# Rbot-sensor-driver.net
KiCad netlist of a schematic drawn in Altium Designer
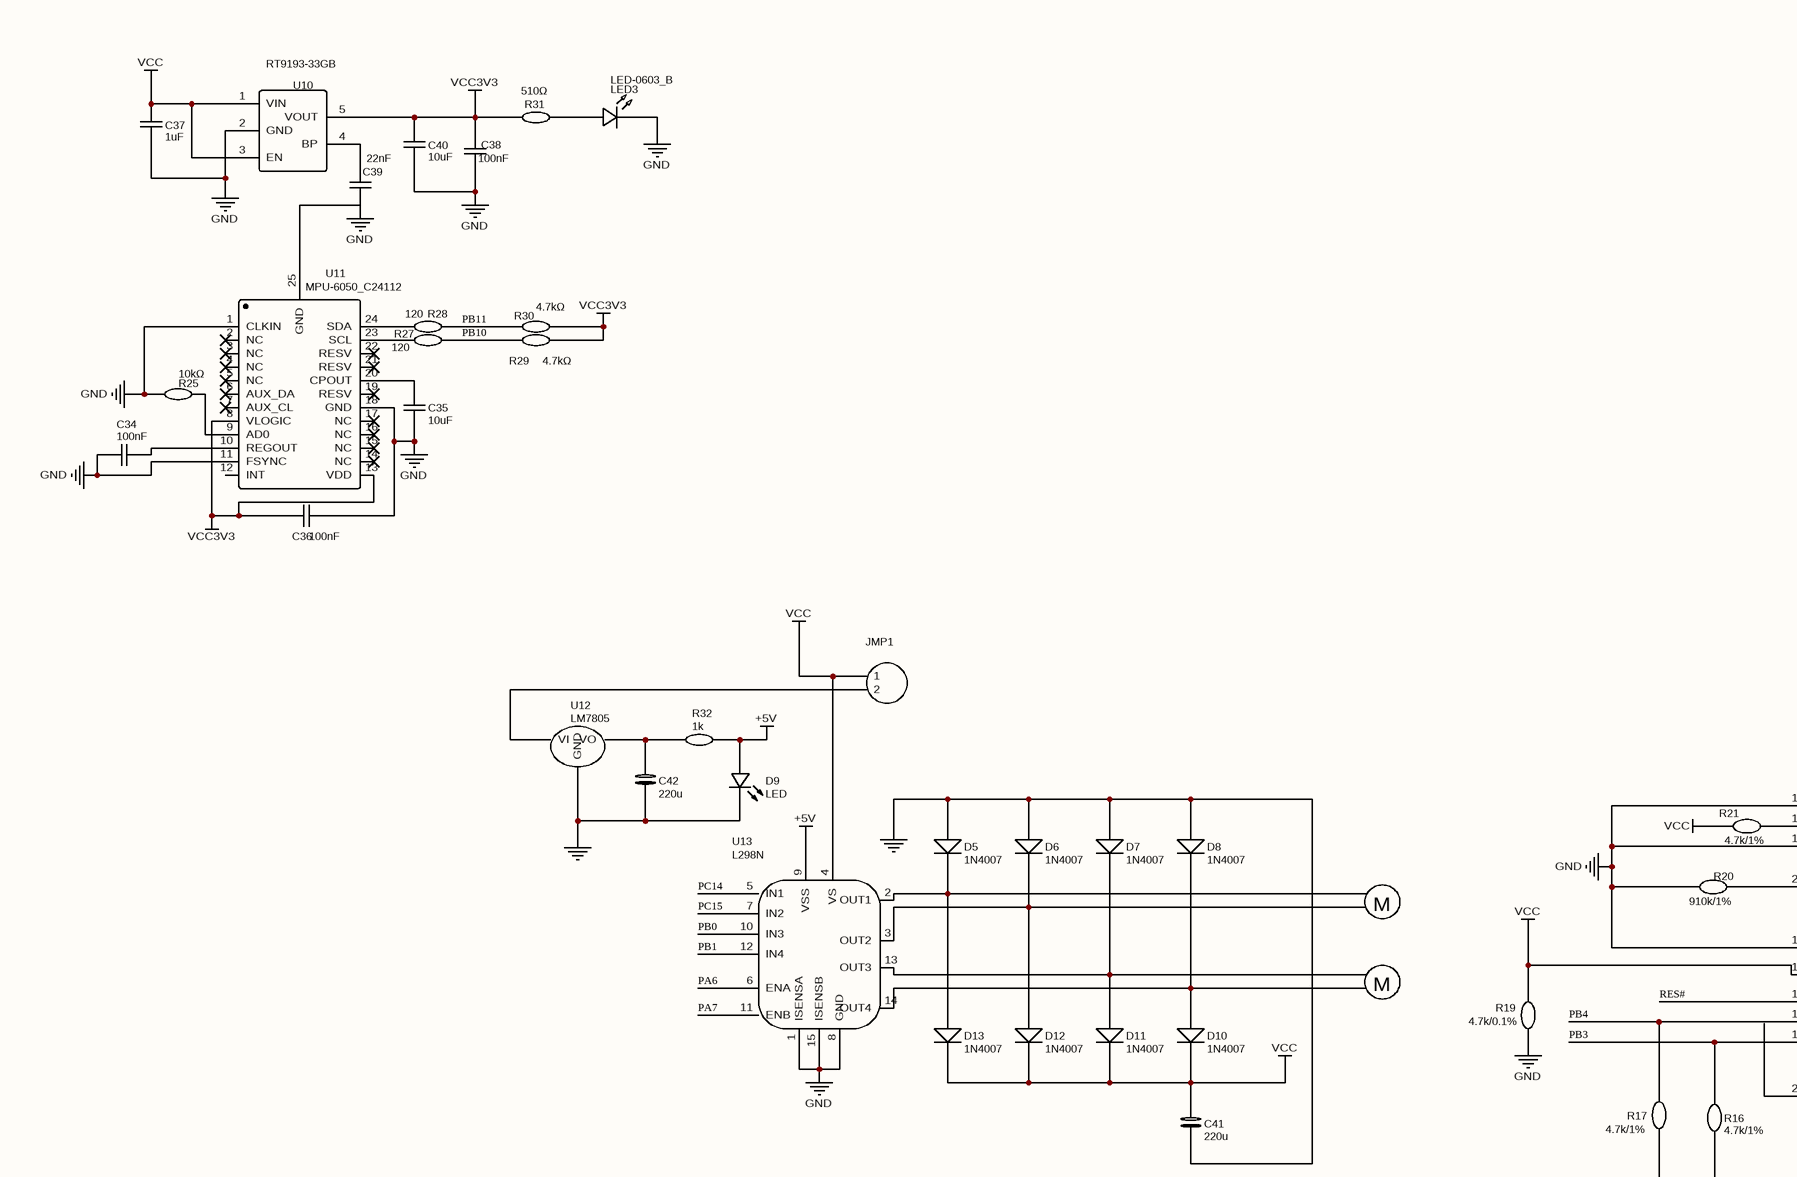
[diagram p0: Rbot-sensor-driver.schdoc, top left]
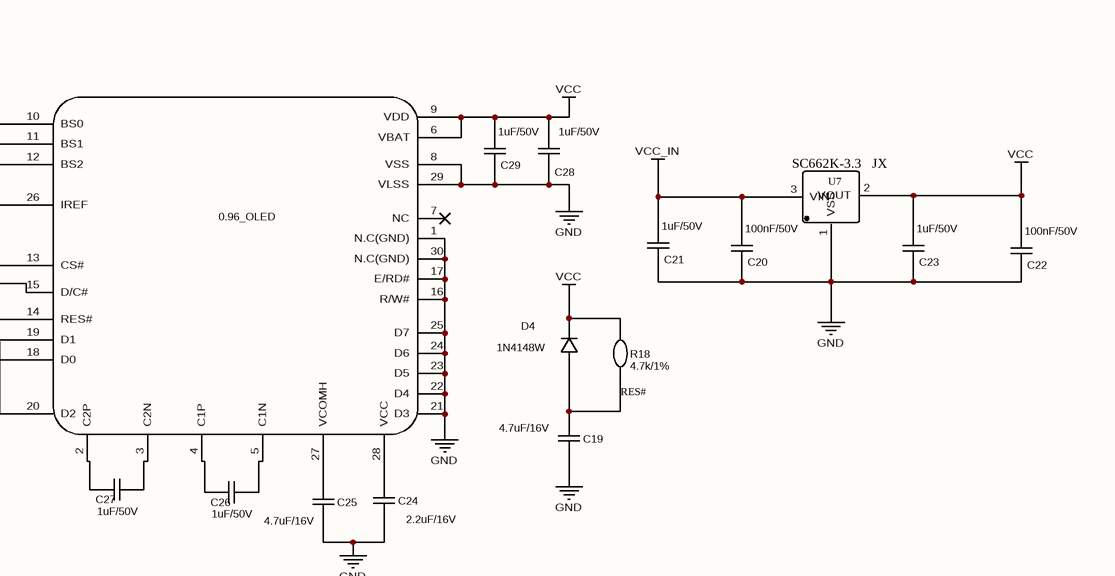
[diagram p1: Rbot-sensor-driver.schdoc, top right]
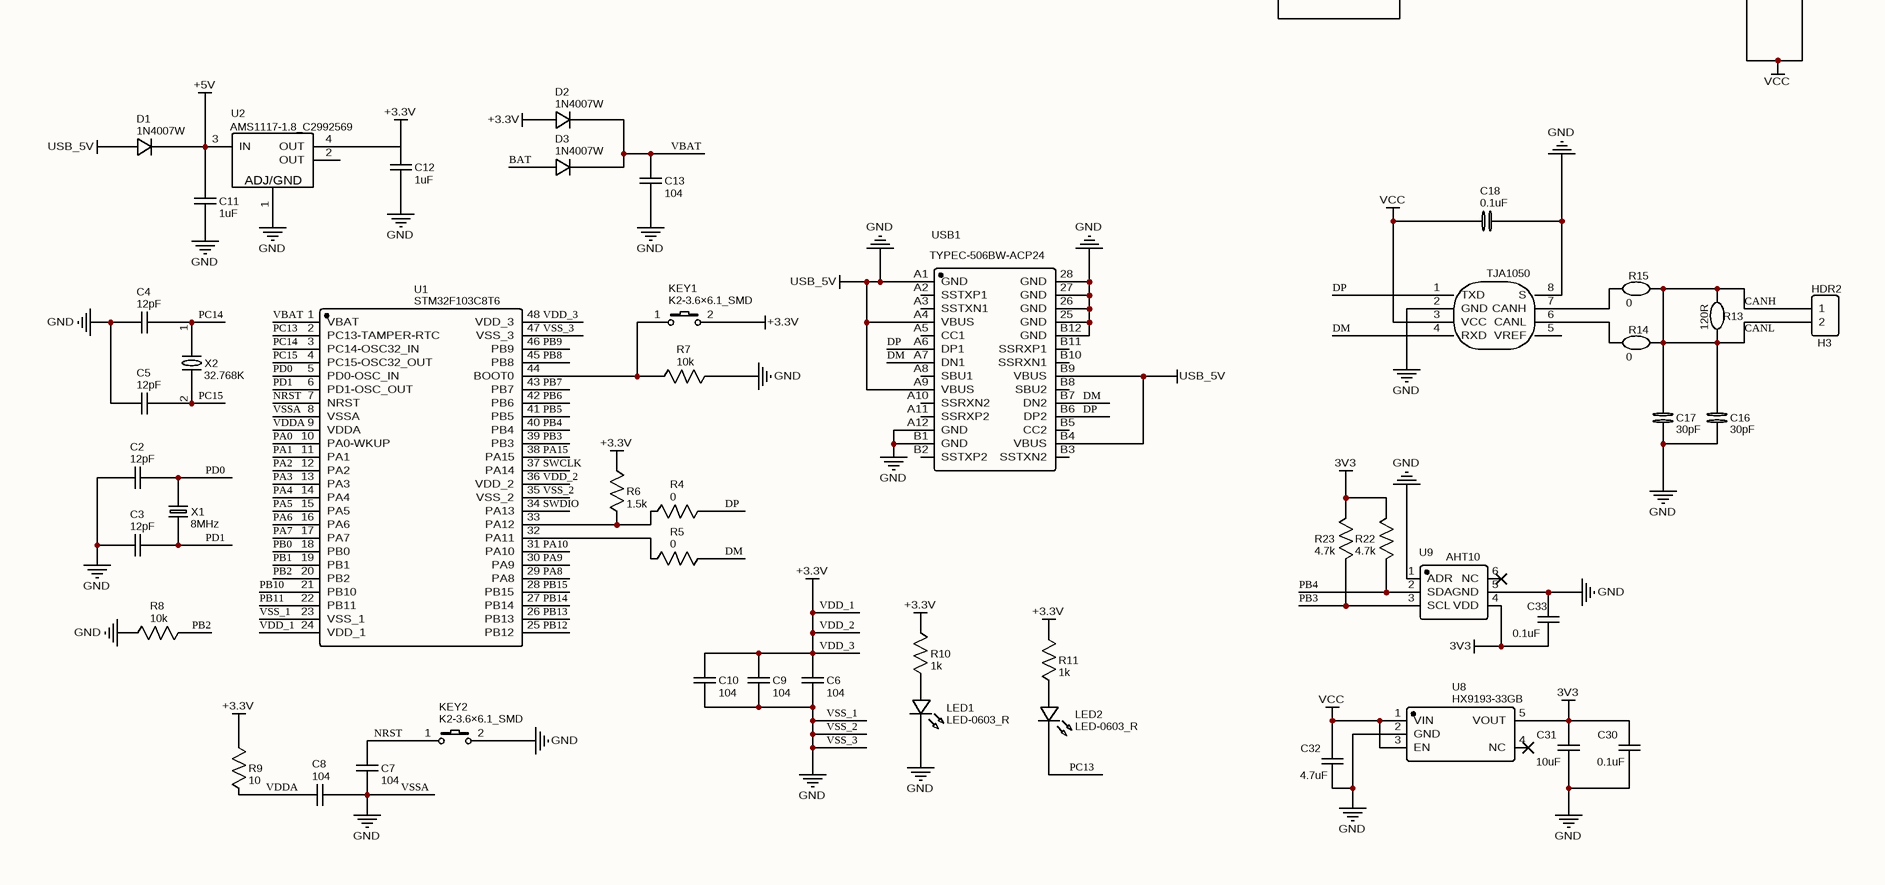
[diagram p2: Rbot-sensor-driver.schdoc, bottom left]

(export (version "E")
  (design (tool "Eeschema 10.0.6"))
  (components
    (comp (ref "0.96_OLED")
      (value "0.96-OLED")
      (footprint "SSD1306-30PIN-JX")
      (libsource (lib "altium-import") (part "root_0_0.96-OLED_"))
    )
    (comp (ref "C2")
      (value "12pF")
      (footprint "C0603")
      (libsource (lib "altium-import") (part "root_0_12pF_"))
    )
    (comp (ref "C3")
      (value "12pF")
      (footprint "C0603")
      (libsource (lib "altium-import") (part "root_0_12pF_"))
    )
    (comp (ref "C4")
      (value "12pF")
      (footprint "C0603")
      (libsource (lib "altium-import") (part "root_0_12pF_"))
    )
    (comp (ref "C5")
      (value "12pF")
      (footprint "C0603")
      (libsource (lib "altium-import") (part "root_0_12pF_"))
    )
    (comp (ref "C6") (value "104") (footprint "C0603") (libsource (lib "altium-import") (part "root_1_104_")))
    (comp (ref "C7") (value "104") (footprint "C0603") (libsource (lib "altium-import") (part "root_1_104_")))
    (comp (ref "C8") (value "104") (footprint "C0603") (libsource (lib "altium-import") (part "root_2_104_")))
    (comp (ref "C9") (value "104") (footprint "C0603") (libsource (lib "altium-import") (part "root_1_104_")))
    (comp (ref "C10")
      (value "104")
      (footprint "C0603")
      (libsource (lib "altium-import") (part "root_1_104_"))
    )
    (comp (ref "C11")
      (value "1uF")
      (footprint "C0603")
      (libsource (lib "altium-import") (part "root_3_1uF_"))
    )
    (comp (ref "C12")
      (value "1uF")
      (footprint "C0603")
      (libsource (lib "altium-import") (part "root_3_1uF_"))
    )
    (comp (ref "C13")
      (value "104")
      (footprint "C0603")
      (libsource (lib "altium-import") (part "root_3_104_"))
    )
    (comp (ref "C16")
      (value "30pF")
      (footprint "C0603")
      (libsource (lib "altium-import") (part "root_1_30pF_"))
    )
    (comp (ref "C17")
      (value "30pF")
      (footprint "C0603")
      (libsource (lib "altium-import") (part "root_1_30pF_"))
    )
    (comp (ref "C18")
      (value "0.1uF")
      (footprint "C0603")
      (libsource (lib "altium-import") (part "root_0_0.1uF_"))
    )
    (comp (ref "C19")
      (value "4.7uF/16V")
      (footprint "0603_C_JX")
      (libsource (lib "altium-import") (part "root_2_4.7uF/16V_"))
    )
    (comp (ref "C20")
      (value "100nF/50V")
      (footprint "0603_C_JX")
      (libsource (lib "altium-import") (part "root_0_100nF/50V_"))
    )
    (comp (ref "C21")
      (value "1uF/50V")
      (footprint "0603_C_JX")
      (libsource (lib "altium-import") (part "root_0_1uF/50V_"))
    )
    (comp (ref "C22")
      (value "100nF/50V")
      (footprint "0603_C_JX")
      (libsource (lib "altium-import") (part "root_0_100nF/50V_"))
    )
    (comp (ref "C23")
      (value "1uF/50V")
      (footprint "0603_C_JX")
      (libsource (lib "altium-import") (part "root_0_1uF/50V_"))
    )
    (comp (ref "C24")
      (value "2.2uF/16V")
      (footprint "0603_C_JX")
      (libsource (lib "altium-import") (part "root_2_2.2uF/16V_"))
    )
    (comp (ref "C25")
      (value "4.7uF/16V")
      (footprint "0603_C_JX")
      (libsource (lib "altium-import") (part "root_2_4.7uF/16V_"))
    )
    (comp (ref "C26")
      (value "1uF/50V")
      (footprint "0603_C_JX")
      (libsource (lib "altium-import") (part "root_1_1uF/50V_"))
    )
    (comp (ref "C27")
      (value "1uF/50V")
      (footprint "0603_C_JX")
      (libsource (lib "altium-import") (part "root_1_1uF/50V_"))
    )
    (comp (ref "C28")
      (value "1uF/50V")
      (footprint "0603_C_JX")
      (libsource (lib "altium-import") (part "root_0_1uF/50V_"))
    )
    (comp (ref "C29")
      (value "1uF/50V")
      (footprint "0603_C_JX")
      (libsource (lib "altium-import") (part "root_0_1uF/50V_"))
    )
    (comp (ref "C30")
      (value "0.1uF")
      (footprint "C0402")
      (libsource (lib "altium-import") (part "root_1_0.1uF_"))
    )
    (comp (ref "C31")
      (value "10uF")
      (footprint "C0402")
      (libsource (lib "altium-import") (part "root_1_10uF_"))
    )
    (comp (ref "C32")
      (value "4.7uF")
      (footprint "C0402")
      (libsource (lib "altium-import") (part "root_1_4.7uF_"))
    )
    (comp (ref "C33")
      (value "0.1uF")
      (footprint "C0402")
      (libsource (lib "altium-import") (part "root_1_0.1uF_"))
    )
    (comp (ref "C34")
      (value "100nF")
      (footprint "C0805")
      (fields
        (field (name "MANUFACTURER") "HEC(Holy Stone Enterprise)")
        (field (name "MANUFACTURER PART") "C0805X104K101T")
      )
      (libsource (lib "altium-import") (part "root_1_100nF_"))
    )
    (comp (ref "C35")
      (value "10uF")
      (footprint "C0805")
      (fields
        (field (name "MANUFACTURER") "muRata(村田)")
        (field (name "MANUFACTURER PART") "GRT21BC71E106KE13L")
      )
      (libsource (lib "altium-import") (part "root_1_10uF_"))
    )
    (comp (ref "C36")
      (value "100nF")
      (footprint "C0805")
      (fields
        (field (name "MANUFACTURER") "HEC(Holy Stone Enterprise)")
        (field (name "MANUFACTURER PART") "C0805X104K101T")
      )
      (libsource (lib "altium-import") (part "root_1_100nF_"))
    )
    (comp (ref "C37")
      (value "1uF")
      (footprint "C0805")
      (fields (field (name "MANUFACTURER PART") "CL21F105ZBFNNNE") (field (name "MANUFACTURER") "SAMSUNG"))
      (libsource (lib "altium-import") (part "root_1_1uF_"))
    )
    (comp (ref "C38")
      (value "100nF")
      (footprint "C0805")
      (fields
        (field (name "MANUFACTURER") "HEC(Holy Stone Enterprise)")
        (field (name "MANUFACTURER PART") "C0805X104K101T")
      )
      (libsource (lib "altium-import") (part "root_0_100nF_"))
    )
    (comp (ref "C39")
      (value "22nF")
      (footprint "C0805")
      (fields (field (name "MANUFACTURER") "Huaxin S&T") (field (name "MANUFACTURER PART") "0805B223K251CT"))
      (libsource (lib "altium-import") (part "root_0_22nF_"))
    )
    (comp (ref "C40")
      (value "10uF")
      (footprint "C0805")
      (fields
        (field (name "MANUFACTURER") "muRata(村田)")
        (field (name "MANUFACTURER PART") "GRT21BC71E106KE13L")
      )
      (libsource (lib "altium-import") (part "root_1_10uF_"))
    )
    (comp (ref "C41")
      (value "220u")
      (footprint "CP_8X13MM")
      (fields (field (name "MANUFACTURER PART") "?"))
      (libsource (lib "altium-import") (part "root_0_220u_"))
    )
    (comp (ref "C42")
      (value "220u")
      (footprint "CP_8X13MM")
      (fields (field (name "MANUFACTURER PART") "?"))
      (libsource (lib "altium-import") (part "root_0_220u_"))
    )
    (comp (ref "D1")
      (value "1N4007W")
      (footprint "SOD-123_L2.8-W1.8-LS3.7-RD")
      (fields (field (name "MANUFACTURER") "BLUE ROCKET"))
      (libsource (lib "altium-import") (part "root_0_1N4007W_"))
    )
    (comp (ref "D2")
      (value "1N4007W")
      (footprint "SOD-123_L2.8-W1.8-LS3.7-RD")
      (fields (field (name "MANUFACTURER") "BLUE ROCKET"))
      (libsource (lib "altium-import") (part "root_0_1N4007W_"))
    )
    (comp (ref "D3")
      (value "1N4007W")
      (footprint "SOD-123_L2.8-W1.8-LS3.7-RD")
      (fields (field (name "MANUFACTURER") "BLUE ROCKET"))
      (libsource (lib "altium-import") (part "root_0_1N4007W_"))
    )
    (comp (ref "D4")
      (value "1N4148W")
      (footprint "SOD-523_JX")
      (fields (field (name "MANUFACTURER") "SEMTECH"))
      (libsource (lib "altium-import") (part "root_3_1N4148W_"))
    )
    (comp (ref "D5")
      (value "1N4007")
      (footprint "DO-41")
      (fields (field (name "MANUFACTURER PART") "?"))
      (libsource (lib "altium-import") (part "root_3_1N4007_"))
    )
    (comp (ref "D6")
      (value "1N4007")
      (footprint "DO-41")
      (fields (field (name "MANUFACTURER PART") "?"))
      (libsource (lib "altium-import") (part "root_3_1N4007_"))
    )
    (comp (ref "D7")
      (value "1N4007")
      (footprint "DO-41")
      (fields (field (name "MANUFACTURER PART") "?"))
      (libsource (lib "altium-import") (part "root_3_1N4007_"))
    )
    (comp (ref "D8")
      (value "1N4007")
      (footprint "DO-41")
      (fields (field (name "MANUFACTURER PART") "?"))
      (libsource (lib "altium-import") (part "root_3_1N4007_"))
    )
    (comp (ref "D9")
      (value "LED")
      (footprint "LED3MM")
      (fields (field (name "MANUFACTURER PART") "?"))
      (libsource (lib "altium-import") (part "root_3_LED_"))
    )
    (comp (ref "D10")
      (value "1N4007")
      (footprint "DO-41")
      (fields (field (name "MANUFACTURER PART") "?"))
      (libsource (lib "altium-import") (part "root_3_1N4007_"))
    )
    (comp (ref "D11")
      (value "1N4007")
      (footprint "DO-41")
      (fields (field (name "MANUFACTURER PART") "?"))
      (libsource (lib "altium-import") (part "root_3_1N4007_"))
    )
    (comp (ref "D12")
      (value "1N4007")
      (footprint "DO-41")
      (fields (field (name "MANUFACTURER PART") "?"))
      (libsource (lib "altium-import") (part "root_3_1N4007_"))
    )
    (comp (ref "D13")
      (value "1N4007")
      (footprint "DO-41")
      (fields (field (name "MANUFACTURER PART") "?"))
      (libsource (lib "altium-import") (part "root_3_1N4007_"))
    )
    (comp (ref "H3")
      (value "HDR2")
      (footprint "HDR-F-2.54_1X2")
      (libsource (lib "altium-import") (part "root_0_HDR2_"))
    )
    (comp (ref "JMP1")
      (value "SIP2")
      (footprint "HDR1X2")
      (fields (field (name "MANUFACTURER PART") "?"))
      (libsource (lib "altium-import") (part "root_0_SIP2_"))
    )
    (comp (ref "KEY1")
      (value "K2-3.6×6.1_SMD")
      (footprint "KEY-SMD_2P-L6.2-W3.6-LS8.0")
      (fields (field (name "MANUFACTURER PART") "K2-1107ST-A4SW-06"))
      (libsource (lib "altium-import") (part "root_0_K2-3.6×6.1_SMD_"))
    )
    (comp (ref "KEY2")
      (value "K2-3.6×6.1_SMD")
      (footprint "KEY-SMD_2P-L6.2-W3.6-LS8.0")
      (fields (field (name "MANUFACTURER PART") "K2-1107ST-A4SW-06"))
      (libsource (lib "altium-import") (part "root_0_K2-3.6×6.1_SMD_"))
    )
    (comp (ref "LED1")
      (value "LED-0603_R")
      (footprint "LED0603_RED")
      (fields
        (field (name "MANUFACTURER") "EVERLIGHT(台湾亿光)")
        (field (name "MANUFACTURER PART") "19-217/R6C-AL1M2VY/3T")
      )
      (libsource (lib "altium-import") (part "root_3_LED-0603_R_"))
    )
    (comp (ref "LED2")
      (value "LED-0603_R")
      (footprint "LED0603_RED")
      (fields
        (field (name "MANUFACTURER") "EVERLIGHT(台湾亿光)")
        (field (name "MANUFACTURER PART") "19-217/R6C-AL1M2VY/3T")
      )
      (libsource (lib "altium-import") (part "root_3_LED-0603_R_"))
    )
    (comp (ref "LED3")
      (value "LED-0603_B")
      (footprint "LED0603_BLUE")
      (fields
        (field (name "MANUFACTURER") "EVERLIGHT(台湾亿光)")
        (field (name "MANUFACTURER PART") "19-217/BHC-ZL1M2RY/3T")
      )
      (libsource (lib "altium-import") (part "root_0_LED-0603_B_"))
    )
    (comp (ref "R4") (value "0") (footprint "R0603") (libsource (lib "altium-import") (part "root_0_0_")))
    (comp (ref "R5") (value "0") (footprint "R0603") (libsource (lib "altium-import") (part "root_0_0_")))
    (comp (ref "R6")
      (value "1.5k")
      (footprint "R0603")
      (libsource (lib "altium-import") (part "root_1_1.5k_"))
    )
    (comp (ref "R7") (value "10k") (footprint "R0603") (libsource (lib "altium-import") (part "root_0_10k_")))
    (comp (ref "R8") (value "10k") (footprint "R0603") (libsource (lib "altium-import") (part "root_0_10k_")))
    (comp (ref "R9") (value "10") (footprint "R0603") (libsource (lib "altium-import") (part "root_3_10_")))
    (comp (ref "R10") (value "1k") (footprint "R0603") (libsource (lib "altium-import") (part "root_3_1k_")))
    (comp (ref "R11") (value "1k") (footprint "R0603") (libsource (lib "altium-import") (part "root_3_1k_")))
    (comp (ref "R13")
      (value "120R")
      (footprint "R0603")
      (libsource (lib "altium-import") (part "root_1_120R_"))
    )
    (comp (ref "R14") (value "0") (footprint "R0603") (libsource (lib "") (part "root_0_0__1")))
    (comp (ref "R15") (value "0") (footprint "R0603") (libsource (lib "") (part "root_0_0__1")))
    (comp (ref "R16")
      (value "4.7k/1%")
      (footprint "0603_R_JX")
      (libsource (lib "altium-import") (part "root_1_4.7k/1%_"))
    )
    (comp (ref "R17")
      (value "4.7k/1%")
      (footprint "0603_R_JX")
      (libsource (lib "altium-import") (part "root_1_4.7k/1%_"))
    )
    (comp (ref "R18")
      (value "4.7k/1%")
      (footprint "0603_R_JX")
      (libsource (lib "altium-import") (part "root_1_4.7k/1%_"))
    )
    (comp (ref "R19")
      (value "4.7k/0.1%")
      (footprint "0603_R_JX")
      (libsource (lib "altium-import") (part "root_1_4.7k/0.1%_"))
    )
    (comp (ref "R20")
      (value "910k/1%")
      (footprint "0603_R_JX")
      (libsource (lib "altium-import") (part "root_0_910k/1%_"))
    )
    (comp (ref "R21")
      (value "4.7k/1%")
      (footprint "0603_R_JX")
      (libsource (lib "altium-import") (part "root_0_4.7k/1%_"))
    )
    (comp (ref "R22")
      (value "4.7k")
      (footprint "R0402")
      (libsource (lib "altium-import") (part "root_1_4.7k_"))
    )
    (comp (ref "R23")
      (value "4.7k")
      (footprint "R0402")
      (libsource (lib "altium-import") (part "root_1_4.7k_"))
    )
    (comp (ref "R25")
      (value "10kΩ")
      (footprint "R0805")
      (fields (field (name "MANUFACTURER") "Viking Tech") (field (name "MANUFACTURER PART") "AR05BTDW1002"))
      (libsource (lib "altium-import") (part "root_0_10kΩ_"))
    )
    (comp (ref "R27")
      (value "120")
      (footprint "R0805")
      (fields (field (name "MANUFACTURER") "YAGEO") (field (name "MANUFACTURER PART") "RC0805JR-07120RL"))
      (libsource (lib "altium-import") (part "root_0_120_"))
    )
    (comp (ref "R28")
      (value "120")
      (footprint "R0805")
      (fields (field (name "MANUFACTURER") "YAGEO") (field (name "MANUFACTURER PART") "RC0805JR-07120RL"))
      (libsource (lib "altium-import") (part "root_0_120_"))
    )
    (comp (ref "R29")
      (value "4.7kΩ")
      (footprint "R0805")
      (fields (field (name "MANUFACTURER") "Tyohm") (field (name "MANUFACTURER PART") "RMC08054.7K1%N"))
      (libsource (lib "altium-import") (part "root_0_4.7kΩ_"))
    )
    (comp (ref "R30")
      (value "4.7kΩ")
      (footprint "R0805")
      (fields (field (name "MANUFACTURER") "Tyohm") (field (name "MANUFACTURER PART") "RMC08054.7K1%N"))
      (libsource (lib "altium-import") (part "root_0_4.7kΩ_"))
    )
    (comp (ref "R31")
      (value "510Ω")
      (footprint "R0805")
      (fields (field (name "MANUFACTURER") "UniOhm") (field (name "MANUFACTURER PART") "0805W8J0511T5E"))
      (libsource (lib "altium-import") (part "root_0_510Ω_"))
    )
    (comp (ref "R32")
      (value "1k")
      (footprint "R3")
      (fields (field (name "MANUFACTURER PART") "?"))
      (libsource (lib "altium-import") (part "root_0_1k_"))
    )
    (comp (ref "U1")
      (value "STM32F103C8T6")
      (footprint "LQFP-48_L7.0-W7.0-P0.50-LS9.0-BL")
      (fields (field (name "MANUFACTURER") "ST(意法半导体)"))
      (libsource (lib "altium-import") (part "root_0_STM32F103C8T6_"))
    )
    (comp (ref "U2")
      (value "AMS1117-1.8_C2992569")
      (footprint "SOT-223-3_L6.4-W3.5-P2.30-LS7.0-BR")
      (fields (field (name "MANUFACTURER") "国芯佳品") (field (name "MANUFACTURER PART") "AMS1117-1.8"))
      (libsource (lib "altium-import") (part "root_0_AMS1117-1.8_C2992569_"))
    )
    (comp (ref "U6")
      (value "TJA1050")
      (footprint "SOIC-8_L5.0-W4.0-P1.27-LS6.0-BL")
      (fields (field (name "MANUFACTURER") "NXP") (field (name "MANUFACTURER PART") "TJA1050T/CM,118"))
      (libsource (lib "altium-import") (part "root_0_TJA1050_"))
    )
    (comp (ref "U7")
      (value "SC662K-3.3   JX")
      (footprint "SOT23_JX")
      (libsource (lib "altium-import") (part "root_1_SC662K-3.3   JX_"))
    )
    (comp (ref "U8")
      (value "HX9193-33GB")
      (footprint "SOT-23-5_L3.0-W1.7-P0.95-LS2.8-BR")
      (fields (field (name "MANUFACTURER") "hengjiaxing"))
      (libsource (lib "altium-import") (part "root_0_HX9193-33GB_"))
    )
    (comp (ref "U9")
      (value "AHT10")
      (footprint "AHT10-SMD-6")
      (fields (field (name "MANUFACTURER") "广州奥松"))
      (libsource (lib "altium-import") (part "root_0_AHT10_"))
    )
    (comp (ref "U10")
      (value "RT9193-33GB")
      (footprint "SOT-23-5_L3.0-W1.7-P0.95-LS2.8-BR")
      (fields (field (name "MANUFACTURER") "RICHTEK"))
      (libsource (lib "altium-import") (part "root_0_RT9193-33GB_"))
    )
    (comp (ref "U11")
      (value "MPU-6050_C24112")
      (footprint "QFN-24_L4.0-W4.0-P0.50-BL-EP2.7")
      (fields (field (name "MANUFACTURER") "InvenSense") (field (name "MANUFACTURER PART") "MPU-6050"))
      (libsource (lib "altium-import") (part "root_0_MPU-6050_C24112_"))
    )
    (comp (ref "U12")
      (value "LM7805")
      (footprint "NONE")
      (fields (field (name "MANUFACTURER PART") "?"))
      (libsource (lib "altium-import") (part "root_0_LM7805_"))
    )
    (comp (ref "U13")
      (value "L298N")
      (footprint "NONE")
      (fields (field (name "MANUFACTURER PART") "?"))
      (libsource (lib "altium-import") (part "root_0_L298N_"))
    )
    (comp (ref "USB1")
      (value "TYPEC-506BW-ACP24")
      (footprint "USB-C-SMD_TYPEC-506BW-ACP24")
      (fields (field (name "MANUFACTURER") "XUNPU(讯普)"))
      (libsource (lib "altium-import") (part "root_0_TYPEC-506BW-ACP24_"))
    )
    (comp (ref "X1")
      (value "8MHz")
      (footprint "HC-49S_L11.4-W4.8")
      (fields
        (field (name "MANUFACTURER") "TAITIEN(泰艺电子)")
        (field (name "MANUFACTURER PART") "XJHCELNANF-8M")
      )
      (libsource (lib "altium-import") (part "root_1_8MHz_"))
    )
    (comp (ref "X2")
      (value "32.768K")
      (footprint "OSC-SMD_2P-L3.2-W1.5-1")
      (fields (field (name "MANUFACTURER PART") "贴片晶振32.768k"))
      (libsource (lib "altium-import") (part "root_3_32.768K_"))
    )
  )
  (nets
    (net (code "1") (name "+3.3V") (class "Default")
      (node (ref "C10") (pin "2") (pinfunction "2_2") (pintype "passive"))
      (node (ref "C12") (pin "1") (pinfunction "1_1") (pintype "passive"))
      (node (ref "C6") (pin "2") (pinfunction "2_2") (pintype "passive"))
      (node (ref "C9") (pin "2") (pinfunction "2_2") (pintype "passive"))
      (node (ref "D2") (pin "2") (pinfunction "2_2") (pintype "passive"))
      (node (ref "KEY1") (pin "2") (pinfunction "2_2") (pintype "passive"))
      (node (ref "R10") (pin "1") (pinfunction "1_1") (pintype "passive"))
      (node (ref "R11") (pin "1") (pinfunction "1_1") (pintype "passive"))
      (node (ref "R6") (pin "2") (pinfunction "2_2") (pintype "passive"))
      (node (ref "R9") (pin "1") (pinfunction "1_1") (pintype "passive"))
      (node (ref "U1") (pin "24") (pinfunction "VDD_1_24") (pintype "passive"))
      (node (ref "U1") (pin "36") (pinfunction "VDD_2_36") (pintype "passive"))
      (node (ref "U1") (pin "48") (pinfunction "VDD_3_48") (pintype "passive"))
    )
    (net (code "2") (name "+5V") (class "Default")
      (node (ref "C11") (pin "1") (pinfunction "1_1") (pintype "passive"))
      (node (ref "D1") (pin "1") (pinfunction "1_1") (pintype "passive"))
      (node (ref "D9") (pin "A") (pinfunction "A_A") (pintype "passive"))
      (node (ref "R32") (pin "2") (pinfunction "2_2") (pintype "passive"))
      (node (ref "U13") (pin "9") (pinfunction "VSS_9") (pintype "passive"))
      (node (ref "U2") (pin "3") (pinfunction "IN_3") (pintype "passive"))
    )
    (net (code "3") (name "/BAT") (class "Default")
      (node (ref "D3") (pin "2") (pinfunction "2_2") (pintype "passive"))
    )
    (net (code "4") (name "/CANH") (class "Default")
      (node (ref "C16") (pin "2") (pinfunction "2_2") (pintype "passive"))
      (node (ref "C17") (pin "2") (pinfunction "2_2") (pintype "passive"))
      (node (ref "H3") (pin "1") (pinfunction "1_1") (pintype "passive"))
      (node (ref "H3") (pin "2") (pinfunction "2_2") (pintype "passive"))
      (node (ref "R13") (pin "1") (pinfunction "1_1") (pintype "passive"))
      (node (ref "R13") (pin "2") (pinfunction "2_2") (pintype "passive"))
      (node (ref "R14") (pin "2") (pinfunction "2_2") (pintype "passive"))
      (node (ref "R15") (pin "2") (pinfunction "2_2") (pintype "passive"))
    )
    (net (code "5") (name "/DM") (class "Default")
      (node (ref "R5") (pin "2") (pinfunction "2_2") (pintype "passive"))
      (node (ref "U6") (pin "4") (pinfunction "RXD_4") (pintype "passive"))
      (node (ref "USB1") (pin "A7") (pinfunction "DN1_A7") (pintype "passive"))
      (node (ref "USB1") (pin "B7") (pinfunction "DN2_B7") (pintype "passive"))
    )
    (net (code "6") (name "/DP") (class "Default")
      (node (ref "R4") (pin "2") (pinfunction "2_2") (pintype "passive"))
      (node (ref "U6") (pin "1") (pinfunction "TXD_1") (pintype "passive"))
      (node (ref "USB1") (pin "A6") (pinfunction "DP1_A6") (pintype "passive"))
      (node (ref "USB1") (pin "B6") (pinfunction "DP2_B6") (pintype "passive"))
    )
    (net (code "7") (name "/NRST") (class "Default")
      (node (ref "C7") (pin "2") (pinfunction "2_2") (pintype "passive"))
      (node (ref "KEY2") (pin "1") (pinfunction "1_1") (pintype "passive"))
      (node (ref "U1") (pin "7") (pinfunction "NRST_7") (pintype "passive"))
    )
    (net (code "8") (name "/PA0") (class "Default")
      (node (ref "U1") (pin "10") (pinfunction "PA0-WKUP_10") (pintype "passive"))
    )
    (net (code "9") (name "/PA1") (class "Default")
      (node (ref "U1") (pin "11") (pinfunction "PA1_11") (pintype "passive"))
    )
    (net (code "10") (name "/PA2") (class "Default")
      (node (ref "U1") (pin "12") (pinfunction "PA2_12") (pintype "passive"))
    )
    (net (code "11") (name "/PA3") (class "Default")
      (node (ref "U1") (pin "13") (pinfunction "PA3_13") (pintype "passive"))
    )
    (net (code "12") (name "/PA4") (class "Default")
      (node (ref "U1") (pin "14") (pinfunction "PA4_14") (pintype "passive"))
    )
    (net (code "13") (name "/PA5") (class "Default")
      (node (ref "U1") (pin "15") (pinfunction "PA5_15") (pintype "passive"))
    )
    (net (code "14") (name "/PA6") (class "Default")
      (node (ref "U1") (pin "16") (pinfunction "PA6_16") (pintype "passive"))
      (node (ref "U13") (pin "6") (pinfunction "ENA_6") (pintype "passive"))
    )
    (net (code "15") (name "/PA7") (class "Default")
      (node (ref "U1") (pin "17") (pinfunction "PA7_17") (pintype "passive"))
      (node (ref "U13") (pin "11") (pinfunction "ENB_11") (pintype "passive"))
    )
    (net (code "16") (name "/PA8") (class "Default")
      (node (ref "U1") (pin "29") (pinfunction "PA8_29") (pintype "passive"))
    )
    (net (code "17") (name "/PA9") (class "Default")
      (node (ref "U1") (pin "30") (pinfunction "PA9_30") (pintype "passive"))
    )
    (net (code "18") (name "/PA10") (class "Default")
      (node (ref "U1") (pin "31") (pinfunction "PA10_31") (pintype "passive"))
    )
    (net (code "19") (name "/PA15") (class "Default")
      (node (ref "U1") (pin "38") (pinfunction "PA15_38") (pintype "passive"))
    )
    (net (code "20") (name "/PB0") (class "Default")
      (node (ref "U1") (pin "18") (pinfunction "PB0_18") (pintype "passive"))
      (node (ref "U13") (pin "10") (pinfunction "IN3_10") (pintype "passive"))
    )
    (net (code "21") (name "/PB1") (class "Default")
      (node (ref "U1") (pin "19") (pinfunction "PB1_19") (pintype "passive"))
      (node (ref "U13") (pin "12") (pinfunction "IN4_12") (pintype "passive"))
    )
    (net (code "22") (name "/PB2") (class "Default")
      (node (ref "R8") (pin "2") (pinfunction "2_2") (pintype "passive"))
      (node (ref "U1") (pin "20") (pinfunction "PB2_20") (pintype "passive"))
    )
    (net (code "23") (name "/PB3") (class "Default")
      (node (ref "0.96_OLED") (pin "18") (pinfunction "D0_18") (pintype "passive"))
      (node (ref "R16") (pin "2") (pinfunction "2_2") (pintype "passive"))
      (node (ref "R23") (pin "1") (pinfunction "1_1") (pintype "passive"))
      (node (ref "U1") (pin "39") (pinfunction "PB3_39") (pintype "passive"))
      (node (ref "U9") (pin "3") (pinfunction "SCL_3") (pintype "passive"))
    )
    (net (code "24") (name "/PB4") (class "Default")
      (node (ref "0.96_OLED") (pin "19") (pinfunction "D1_19") (pintype "passive"))
      (node (ref "R17") (pin "2") (pinfunction "2_2") (pintype "passive"))
      (node (ref "R22") (pin "1") (pinfunction "1_1") (pintype "passive"))
      (node (ref "U1") (pin "40") (pinfunction "PB4_40") (pintype "passive"))
      (node (ref "U9") (pin "2") (pinfunction "SDA_2") (pintype "passive"))
    )
    (net (code "25") (name "/PB5") (class "Default")
      (node (ref "U1") (pin "41") (pinfunction "PB5_41") (pintype "passive"))
    )
    (net (code "26") (name "/PB6") (class "Default")
      (node (ref "U1") (pin "42") (pinfunction "PB6_42") (pintype "passive"))
    )
    (net (code "27") (name "/PB7") (class "Default")
      (node (ref "U1") (pin "43") (pinfunction "PB7_43") (pintype "passive"))
    )
    (net (code "28") (name "/PB8") (class "Default")
      (node (ref "U1") (pin "45") (pinfunction "PB8_45") (pintype "passive"))
    )
    (net (code "29") (name "/PB9") (class "Default")
      (node (ref "U1") (pin "46") (pinfunction "PB9_46") (pintype "passive"))
    )
    (net (code "30") (name "/PB10") (class "Default")
      (node (ref "R27") (pin "1") (pinfunction "1_1") (pintype "passive"))
      (node (ref "R29") (pin "2") (pinfunction "2_2") (pintype "passive"))
      (node (ref "U1") (pin "21") (pinfunction "PB10_21") (pintype "passive"))
    )
    (net (code "31") (name "/PB11") (class "Default")
      (node (ref "R28") (pin "1") (pinfunction "1_1") (pintype "passive"))
      (node (ref "R30") (pin "2") (pinfunction "2_2") (pintype "passive"))
      (node (ref "U1") (pin "22") (pinfunction "PB11_22") (pintype "passive"))
    )
    (net (code "32") (name "/PB12") (class "Default")
      (node (ref "U1") (pin "25") (pinfunction "PB12_25") (pintype "passive"))
    )
    (net (code "33") (name "/PB13") (class "Default")
      (node (ref "U1") (pin "26") (pinfunction "PB13_26") (pintype "passive"))
    )
    (net (code "34") (name "/PB14") (class "Default")
      (node (ref "U1") (pin "27") (pinfunction "PB14_27") (pintype "passive"))
    )
    (net (code "35") (name "/PB15") (class "Default")
      (node (ref "U1") (pin "28") (pinfunction "PB15_28") (pintype "passive"))
    )
    (net (code "36") (name "/PC13") (class "Default")
      (node (ref "LED2") (pin "2") (pinfunction "2_2") (pintype "passive"))
      (node (ref "U1") (pin "2") (pinfunction "PC13-TAMPER-RTC_2") (pintype "passive"))
    )
    (net (code "37") (name "/PC14") (class "Default")
      (node (ref "C4") (pin "2") (pinfunction "2_2") (pintype "passive"))
      (node (ref "U1") (pin "3") (pinfunction "PC14-OSC32_IN_3") (pintype "passive"))
      (node (ref "U13") (pin "5") (pinfunction "IN1_5") (pintype "passive"))
      (node (ref "X2") (pin "1") (pinfunction "1_1") (pintype "passive"))
    )
    (net (code "38") (name "/PC15") (class "Default")
      (node (ref "C5") (pin "2") (pinfunction "2_2") (pintype "passive"))
      (node (ref "U1") (pin "4") (pinfunction "PC15-OSC32_OUT_4") (pintype "passive"))
      (node (ref "U13") (pin "7") (pinfunction "IN2_7") (pintype "passive"))
      (node (ref "X2") (pin "2") (pinfunction "2_2") (pintype "passive"))
    )
    (net (code "39") (name "/PD0") (class "Default")
      (node (ref "C2") (pin "2") (pinfunction "2_2") (pintype "passive"))
      (node (ref "U1") (pin "5") (pinfunction "PD0-OSC_IN_5") (pintype "passive"))
      (node (ref "X1") (pin "2") (pinfunction "2_2") (pintype "passive"))
    )
    (net (code "40") (name "/PD1") (class "Default")
      (node (ref "C3") (pin "2") (pinfunction "2_2") (pintype "passive"))
      (node (ref "U1") (pin "6") (pinfunction "PD1-OSC_OUT_6") (pintype "passive"))
      (node (ref "X1") (pin "1") (pinfunction "1_1") (pintype "passive"))
    )
    (net (code "41") (name "/RES#") (class "Default")
      (node (ref "0.96_OLED") (pin "14") (pinfunction "RES#_14") (pintype "passive"))
      (node (ref "C19") (pin "1") (pinfunction "1_1") (pintype "passive"))
      (node (ref "D4") (pin "1") (pinfunction "A_1") (pintype "passive"))
      (node (ref "R18") (pin "1") (pinfunction "1_1") (pintype "passive"))
    )
    (net (code "42") (name "/SWCLK") (class "Default")
      (node (ref "U1") (pin "37") (pinfunction "PA14_37") (pintype "passive"))
    )
    (net (code "43") (name "/SWDIO") (class "Default")
      (node (ref "U1") (pin "34") (pinfunction "PA13_34") (pintype "passive"))
    )
    (net (code "44") (name "/VBAT") (class "Default")
      (node (ref "C13") (pin "1") (pinfunction "1_1") (pintype "passive"))
      (node (ref "D2") (pin "1") (pinfunction "1_1") (pintype "passive"))
      (node (ref "D3") (pin "1") (pinfunction "1_1") (pintype "passive"))
      (node (ref "U1") (pin "1") (pinfunction "VBAT_1") (pintype "passive"))
    )
    (net (code "45") (name "/VDDA") (class "Default")
      (node (ref "C8") (pin "2") (pinfunction "2_2") (pintype "passive"))
      (node (ref "R9") (pin "2") (pinfunction "2_2") (pintype "passive"))
      (node (ref "U1") (pin "9") (pinfunction "VDDA_9") (pintype "passive"))
    )
    (net (code "46") (name "3V3") (class "Default")
      (node (ref "C30") (pin "2") (pinfunction "2_2") (pintype "passive"))
      (node (ref "C31") (pin "2") (pinfunction "2_2") (pintype "passive"))
      (node (ref "C33") (pin "1") (pinfunction "1_1") (pintype "passive"))
      (node (ref "R22") (pin "2") (pinfunction "2_2") (pintype "passive"))
      (node (ref "R23") (pin "2") (pinfunction "2_2") (pintype "passive"))
      (node (ref "U8") (pin "5") (pinfunction "VOUT_5") (pintype "passive"))
      (node (ref "U9") (pin "4") (pinfunction "VDD_4") (pintype "passive"))
    )
    (net (code "47") (name "GND") (class "Default")
      (node (ref "0.96_OLED") (pin "1") (pinfunction "N.C(GND)_1") (pintype "passive"))
      (node (ref "0.96_OLED") (pin "10") (pinfunction "BS0_10") (pintype "passive"))
      (node (ref "0.96_OLED") (pin "12") (pinfunction "BS2_12") (pintype "passive"))
      (node (ref "0.96_OLED") (pin "13") (pinfunction "CS#_13") (pintype "passive"))
      (node (ref "0.96_OLED") (pin "16") (pinfunction "R/W#_16") (pintype "passive"))
      (node (ref "0.96_OLED") (pin "17") (pinfunction "E/RD#_17") (pintype "passive"))
      (node (ref "0.96_OLED") (pin "21") (pinfunction "D3_21") (pintype "passive"))
      (node (ref "0.96_OLED") (pin "22") (pinfunction "D4_22") (pintype "passive"))
      (node (ref "0.96_OLED") (pin "23") (pinfunction "D5_23") (pintype "passive"))
      (node (ref "0.96_OLED") (pin "24") (pinfunction "D6_24") (pintype "passive"))
      (node (ref "0.96_OLED") (pin "25") (pinfunction "D7_25") (pintype "passive"))
      (node (ref "0.96_OLED") (pin "29") (pinfunction "VLSS_29") (pintype "passive"))
      (node (ref "0.96_OLED") (pin "30") (pinfunction "N.C(GND)_30") (pintype "passive"))
      (node (ref "0.96_OLED") (pin "8") (pinfunction "VSS_8") (pintype "passive"))
      (node (ref "C10") (pin "1") (pinfunction "1_1") (pintype "passive"))
      (node (ref "C11") (pin "2") (pinfunction "2_2") (pintype "passive"))
      (node (ref "C12") (pin "2") (pinfunction "2_2") (pintype "passive"))
      (node (ref "C13") (pin "2") (pinfunction "2_2") (pintype "passive"))
      (node (ref "C16") (pin "1") (pinfunction "1_1") (pintype "passive"))
      (node (ref "C17") (pin "1") (pinfunction "1_1") (pintype "passive"))
      (node (ref "C18") (pin "2") (pinfunction "2_2") (pintype "passive"))
      (node (ref "C19") (pin "2") (pinfunction "2_2") (pintype "passive"))
      (node (ref "C2") (pin "1") (pinfunction "1_1") (pintype "passive"))
      (node (ref "C20") (pin "1") (pinfunction "1_1") (pintype "passive"))
      (node (ref "C21") (pin "1") (pinfunction "1_1") (pintype "passive"))
      (node (ref "C22") (pin "1") (pinfunction "1_1") (pintype "passive"))
      (node (ref "C23") (pin "1") (pinfunction "1_1") (pintype "passive"))
      (node (ref "C24") (pin "2") (pinfunction "2_2") (pintype "passive"))
      (node (ref "C25") (pin "2") (pinfunction "2_2") (pintype "passive"))
      (node (ref "C28") (pin "1") (pinfunction "1_1") (pintype "passive"))
      (node (ref "C29") (pin "1") (pinfunction "1_1") (pintype "passive"))
      (node (ref "C3") (pin "1") (pinfunction "1_1") (pintype "passive"))
      (node (ref "C30") (pin "1") (pinfunction "1_1") (pintype "passive"))
      (node (ref "C31") (pin "1") (pinfunction "1_1") (pintype "passive"))
      (node (ref "C32") (pin "1") (pinfunction "1_1") (pintype "passive"))
      (node (ref "C33") (pin "2") (pinfunction "2_2") (pintype "passive"))
      (node (ref "C34") (pin "2") (pinfunction "2_2") (pintype "passive"))
      (node (ref "C35") (pin "1") (pinfunction "1_1") (pintype "passive"))
      (node (ref "C36") (pin "1") (pinfunction "1_1") (pintype "passive"))
      (node (ref "C37") (pin "1") (pinfunction "1_1") (pintype "passive"))
      (node (ref "C38") (pin "1") (pinfunction "1_1") (pintype "passive"))
      (node (ref "C4") (pin "1") (pinfunction "1_1") (pintype "passive"))
      (node (ref "C40") (pin "1") (pinfunction "1_1") (pintype "passive"))
      (node (ref "C41") (pin "2") (pinfunction "2_2") (pintype "passive"))
      (node (ref "C42") (pin "2") (pinfunction "2_2") (pintype "passive"))
      (node (ref "C5") (pin "1") (pinfunction "1_1") (pintype "passive"))
      (node (ref "C6") (pin "1") (pinfunction "1_1") (pintype "passive"))
      (node (ref "C7") (pin "1") (pinfunction "1_1") (pintype "passive"))
      (node (ref "C8") (pin "1") (pinfunction "1_1") (pintype "passive"))
      (node (ref "C9") (pin "1") (pinfunction "1_1") (pintype "passive"))
      (node (ref "D1") (pin "2") (pinfunction "2_2") (pintype "passive"))
      (node (ref "D5") (pin "1") (pinfunction "A_1") (pintype "passive"))
      (node (ref "D6") (pin "1") (pinfunction "A_1") (pintype "passive"))
      (node (ref "D7") (pin "1") (pinfunction "A_1") (pintype "passive"))
      (node (ref "D8") (pin "1") (pinfunction "A_1") (pintype "passive"))
      (node (ref "D9") (pin "K") (pinfunction "K_K") (pintype "passive"))
      (node (ref "KEY2") (pin "2") (pinfunction "2_2") (pintype "passive"))
      (node (ref "LED1") (pin "2") (pinfunction "2_2") (pintype "passive"))
      (node (ref "LED3") (pin "2") (pinfunction "2_2") (pintype "passive"))
      (node (ref "R19") (pin "1") (pinfunction "1_1") (pintype "passive"))
      (node (ref "R20") (pin "1") (pinfunction "1_1") (pintype "passive"))
      (node (ref "R25") (pin "1") (pinfunction "1_1") (pintype "passive"))
      (node (ref "R7") (pin "2") (pinfunction "2_2") (pintype "passive"))
      (node (ref "R8") (pin "1") (pinfunction "1_1") (pintype "passive"))
      (node (ref "U1") (pin "23") (pinfunction "VSS_1_23") (pintype "passive"))
      (node (ref "U1") (pin "35") (pinfunction "VSS_2_35") (pintype "passive"))
      (node (ref "U1") (pin "47") (pinfunction "VSS_3_47") (pintype "passive"))
      (node (ref "U1") (pin "8") (pinfunction "VSSA_8") (pintype "passive"))
      (node (ref "U10") (pin "2") (pinfunction "GND_2") (pintype "passive"))
      (node (ref "U11") (pin "1") (pinfunction "CLKIN_1") (pintype "passive"))
      (node (ref "U11") (pin "11") (pinfunction "FSYNC_11") (pintype "passive"))
      (node (ref "U11") (pin "18") (pinfunction "GND_18") (pintype "passive"))
      (node (ref "U11") (pin "25") (pinfunction "GND_25") (pintype "passive"))
      (node (ref "U12") (pin "GND") (pinfunction "GND_GND") (pintype "passive"))
      (node (ref "U13") (pin "1") (pinfunction "ISENSA_1") (pintype "passive"))
      (node (ref "U13") (pin "15") (pinfunction "ISENSB_15") (pintype "passive"))
      (node (ref "U13") (pin "8") (pinfunction "GND_8") (pintype "passive"))
      (node (ref "U2") (pin "1") (pinfunction "ADJ/GND_1") (pintype "passive"))
      (node (ref "U6") (pin "2") (pinfunction "GND_2") (pintype "passive"))
      (node (ref "U6") (pin "8") (pinfunction "S_8") (pintype "passive"))
      (node (ref "U7") (pin "1") (pinfunction "VSS_1") (pintype "passive"))
      (node (ref "U8") (pin "2") (pinfunction "GND_2") (pintype "passive"))
      (node (ref "U9") (pin "1") (pinfunction "ADR_1") (pintype "passive"))
      (node (ref "U9") (pin "5") (pinfunction "GND_5") (pintype "passive"))
      (node (ref "USB1") (pin "25") (pinfunction "GND_25") (pintype "passive"))
      (node (ref "USB1") (pin "26") (pinfunction "GND_26") (pintype "passive"))
      (node (ref "USB1") (pin "27") (pinfunction "GND_27") (pintype "passive"))
      (node (ref "USB1") (pin "28") (pinfunction "GND_28") (pintype "passive"))
      (node (ref "USB1") (pin "A1") (pinfunction "GND_A1") (pintype "passive"))
      (node (ref "USB1") (pin "A12") (pinfunction "GND_A12") (pintype "passive"))
      (node (ref "USB1") (pin "A4") (pinfunction "VBUS_A4") (pintype "passive"))
      (node (ref "USB1") (pin "A9") (pinfunction "VBUS_A9") (pintype "passive"))
      (node (ref "USB1") (pin "B1") (pinfunction "GND_B1") (pintype "passive"))
      (node (ref "USB1") (pin "B12") (pinfunction "GND_B12") (pintype "passive"))
      (node (ref "USB1") (pin "B4") (pinfunction "VBUS_B4") (pintype "passive"))
      (node (ref "USB1") (pin "B9") (pinfunction "VBUS_B9") (pintype "passive"))
    )
    (net (code "48") (name "Net-(0.96_OLED-BS1)") (class "Default")
      (node (ref "0.96_OLED") (pin "11") (pinfunction "BS1_11") (pintype "passive"))
      (node (ref "R21") (pin "2") (pinfunction "2_2") (pintype "passive"))
    )
    (net (code "49") (name "Net-(0.96_OLED-C1N)") (class "Default")
      (node (ref "0.96_OLED") (pin "5") (pinfunction "C1N_5") (pintype "passive"))
      (node (ref "C26") (pin "1") (pinfunction "1_1") (pintype "passive"))
    )
    (net (code "50") (name "Net-(0.96_OLED-C1P)") (class "Default")
      (node (ref "0.96_OLED") (pin "4") (pinfunction "C1P_4") (pintype "passive"))
      (node (ref "C26") (pin "2") (pinfunction "2_2") (pintype "passive"))
    )
    (net (code "51") (name "Net-(0.96_OLED-C2N)") (class "Default")
      (node (ref "0.96_OLED") (pin "3") (pinfunction "C2N_3") (pintype "passive"))
      (node (ref "C27") (pin "1") (pinfunction "1_1") (pintype "passive"))
    )
    (net (code "52") (name "Net-(0.96_OLED-C2P)") (class "Default")
      (node (ref "0.96_OLED") (pin "2") (pinfunction "C2P_2") (pintype "passive"))
      (node (ref "C27") (pin "2") (pinfunction "2_2") (pintype "passive"))
    )
    (net (code "53") (name "Net-(0.96_OLED-IREF)") (class "Default")
      (node (ref "0.96_OLED") (pin "26") (pinfunction "IREF_26") (pintype "passive"))
      (node (ref "R20") (pin "2") (pinfunction "2_2") (pintype "passive"))
    )
    (net (code "54") (name "Net-(0.96_OLED-VCC)") (class "Default")
      (node (ref "0.96_OLED") (pin "28") (pinfunction "VCC_28") (pintype "passive"))
      (node (ref "C24") (pin "1") (pinfunction "1_1") (pintype "passive"))
    )
    (net (code "55") (name "Net-(0.96_OLED-VCOMH)") (class "Default")
      (node (ref "0.96_OLED") (pin "27") (pinfunction "VCOMH_27") (pintype "passive"))
      (node (ref "C25") (pin "1") (pinfunction "1_1") (pintype "passive"))
    )
    (net (code "56") (name "Net-(C42-Pad1)") (class "Default")
      (node (ref "C42") (pin "1") (pinfunction "1_1") (pintype "passive"))
      (node (ref "R32") (pin "1") (pinfunction "1_1") (pintype "passive"))
      (node (ref "U12") (pin "VO") (pinfunction "VO_VO") (pintype "passive"))
    )
    (net (code "57") (name "Net-(D10-A)") (class "Default")
      (node (ref "D10") (pin "1") (pinfunction "A_1") (pintype "passive"))
      (node (ref "D8") (pin "2") (pinfunction "K_2") (pintype "passive"))
      (node (ref "U13") (pin "14") (pinfunction "OUT4_14") (pintype "passive"))
    )
    (net (code "58") (name "Net-(D11-A)") (class "Default")
      (node (ref "D11") (pin "1") (pinfunction "A_1") (pintype "passive"))
      (node (ref "D7") (pin "2") (pinfunction "K_2") (pintype "passive"))
      (node (ref "U13") (pin "13") (pinfunction "OUT3_13") (pintype "passive"))
    )
    (net (code "59") (name "Net-(D12-A)") (class "Default")
      (node (ref "D12") (pin "1") (pinfunction "A_1") (pintype "passive"))
      (node (ref "D6") (pin "2") (pinfunction "K_2") (pintype "passive"))
      (node (ref "U13") (pin "3") (pinfunction "OUT2_3") (pintype "passive"))
    )
    (net (code "60") (name "Net-(D13-A)") (class "Default")
      (node (ref "D13") (pin "1") (pinfunction "A_1") (pintype "passive"))
      (node (ref "D5") (pin "2") (pinfunction "K_2") (pintype "passive"))
      (node (ref "U13") (pin "2") (pinfunction "OUT1_2") (pintype "passive"))
    )
    (net (code "61") (name "Net-(JMP1-Pad2)") (class "Default")
      (node (ref "JMP1") (pin "2") (pinfunction "2_2") (pintype "passive"))
      (node (ref "U12") (pin "VI") (pinfunction "VI_VI") (pintype "passive"))
    )
    (net (code "62") (name "Net-(LED1-Pad1)") (class "Default")
      (node (ref "LED1") (pin "1") (pinfunction "1_1") (pintype "passive"))
      (node (ref "R10") (pin "2") (pinfunction "2_2") (pintype "passive"))
    )
    (net (code "63") (name "Net-(LED2-Pad1)") (class "Default")
      (node (ref "LED2") (pin "1") (pinfunction "1_1") (pintype "passive"))
      (node (ref "R11") (pin "2") (pinfunction "2_2") (pintype "passive"))
    )
    (net (code "64") (name "Net-(LED3-Pad1)") (class "Default")
      (node (ref "LED3") (pin "1") (pinfunction "1_1") (pintype "passive"))
      (node (ref "R31") (pin "2") (pinfunction "2_2") (pintype "passive"))
    )
    (net (code "65") (name "Net-(U1-BOOT0)") (class "Default")
      (node (ref "KEY1") (pin "1") (pinfunction "1_1") (pintype "passive"))
      (node (ref "R7") (pin "1") (pinfunction "1_1") (pintype "passive"))
      (node (ref "U1") (pin "44") (pinfunction "BOOT0_44") (pintype "passive"))
    )
    (net (code "66") (name "Net-(U1-PA11)") (class "Default")
      (node (ref "R5") (pin "1") (pinfunction "1_1") (pintype "passive"))
      (node (ref "U1") (pin "32") (pinfunction "PA11_32") (pintype "passive"))
    )
    (net (code "67") (name "Net-(U1-PA12)") (class "Default")
      (node (ref "R4") (pin "1") (pinfunction "1_1") (pintype "passive"))
      (node (ref "R6") (pin "1") (pinfunction "1_1") (pintype "passive"))
      (node (ref "U1") (pin "33") (pinfunction "PA12_33") (pintype "passive"))
    )
    (net (code "68") (name "Net-(U6-CANH)") (class "Default")
      (node (ref "R15") (pin "1") (pinfunction "1_1") (pintype "passive"))
      (node (ref "U6") (pin "7") (pinfunction "CANH_7") (pintype "passive"))
    )
    (net (code "69") (name "Net-(U6-CANL)") (class "Default")
      (node (ref "R14") (pin "1") (pinfunction "1_1") (pintype "passive"))
      (node (ref "U6") (pin "6") (pinfunction "CANL_6") (pintype "passive"))
    )
    (net (code "70") (name "Net-(U10-BP)") (class "Default")
      (node (ref "C39") (pin "1") (pinfunction "1_1") (pintype "passive"))
      (node (ref "U10") (pin "4") (pinfunction "BP_4") (pintype "passive"))
    )
    (net (code "71") (name "Net-(U11-AD0)") (class "Default")
      (node (ref "R25") (pin "2") (pinfunction "2_2") (pintype "passive"))
      (node (ref "U11") (pin "9") (pinfunction "AD0_9") (pintype "passive"))
    )
    (net (code "72") (name "Net-(U11-CPOUT)") (class "Default")
      (node (ref "C35") (pin "2") (pinfunction "2_2") (pintype "passive"))
      (node (ref "U11") (pin "20") (pinfunction "CPOUT_20") (pintype "passive"))
    )
    (net (code "73") (name "Net-(U11-REGOUT)") (class "Default")
      (node (ref "C34") (pin "1") (pinfunction "1_1") (pintype "passive"))
      (node (ref "U11") (pin "10") (pinfunction "REGOUT_10") (pintype "passive"))
    )
    (net (code "74") (name "Net-(U11-SCL)") (class "Default")
      (node (ref "R27") (pin "2") (pinfunction "2_2") (pintype "passive"))
      (node (ref "U11") (pin "23") (pinfunction "SCL_23") (pintype "passive"))
    )
    (net (code "75") (name "Net-(U11-SDA)") (class "Default")
      (node (ref "R28") (pin "2") (pinfunction "2_2") (pintype "passive"))
      (node (ref "U11") (pin "24") (pinfunction "SDA_24") (pintype "passive"))
    )
    (net (code "76") (name "VCC") (class "Default")
      (node (ref "0.96_OLED") (pin "15") (pinfunction "D/C#_15") (pintype "passive"))
      (node (ref "0.96_OLED") (pin "6") (pinfunction "VBAT_6") (pintype "passive"))
      (node (ref "0.96_OLED") (pin "9") (pinfunction "VDD_9") (pintype "passive"))
      (node (ref "C18") (pin "1") (pinfunction "1_1") (pintype "passive"))
      (node (ref "C22") (pin "2") (pinfunction "2_2") (pintype "passive"))
      (node (ref "C23") (pin "2") (pinfunction "2_2") (pintype "passive"))
      (node (ref "C28") (pin "2") (pinfunction "2_2") (pintype "passive"))
      (node (ref "C29") (pin "2") (pinfunction "2_2") (pintype "passive"))
      (node (ref "C32") (pin "2") (pinfunction "2_2") (pintype "passive"))
      (node (ref "C37") (pin "2") (pinfunction "2_2") (pintype "passive"))
      (node (ref "C41") (pin "1") (pinfunction "1_1") (pintype "passive"))
      (node (ref "D10") (pin "2") (pinfunction "K_2") (pintype "passive"))
      (node (ref "D11") (pin "2") (pinfunction "K_2") (pintype "passive"))
      (node (ref "D12") (pin "2") (pinfunction "K_2") (pintype "passive"))
      (node (ref "D13") (pin "2") (pinfunction "K_2") (pintype "passive"))
      (node (ref "D4") (pin "2") (pinfunction "K_2") (pintype "passive"))
      (node (ref "JMP1") (pin "1") (pinfunction "1_1") (pintype "passive"))
      (node (ref "R16") (pin "1") (pinfunction "1_1") (pintype "passive"))
      (node (ref "R17") (pin "1") (pinfunction "1_1") (pintype "passive"))
      (node (ref "R18") (pin "2") (pinfunction "2_2") (pintype "passive"))
      (node (ref "R19") (pin "2") (pinfunction "2_2") (pintype "passive"))
      (node (ref "R21") (pin "1") (pinfunction "1_1") (pintype "passive"))
      (node (ref "U10") (pin "1") (pinfunction "VIN_1") (pintype "passive"))
      (node (ref "U10") (pin "3") (pinfunction "EN_3") (pintype "passive"))
      (node (ref "U13") (pin "4") (pinfunction "VS_4") (pintype "passive"))
      (node (ref "U6") (pin "3") (pinfunction "VCC_3") (pintype "passive"))
      (node (ref "U7") (pin "2") (pinfunction "VOUT_2") (pintype "passive"))
      (node (ref "U8") (pin "1") (pinfunction "VIN_1") (pintype "passive"))
      (node (ref "U8") (pin "3") (pinfunction "EN_3") (pintype "passive"))
    )
    (net (code "77") (name "VCC3V3") (class "Default")
      (node (ref "C36") (pin "2") (pinfunction "2_2") (pintype "passive"))
      (node (ref "C38") (pin "2") (pinfunction "2_2") (pintype "passive"))
      (node (ref "C40") (pin "2") (pinfunction "2_2") (pintype "passive"))
      (node (ref "R29") (pin "1") (pinfunction "1_1") (pintype "passive"))
      (node (ref "R30") (pin "1") (pinfunction "1_1") (pintype "passive"))
      (node (ref "R31") (pin "1") (pinfunction "1_1") (pintype "passive"))
      (node (ref "U10") (pin "5") (pinfunction "VOUT_5") (pintype "passive"))
      (node (ref "U11") (pin "13") (pinfunction "VDD_13") (pintype "passive"))
      (node (ref "U11") (pin "8") (pinfunction "VLOGIC_8") (pintype "passive"))
    )
    (net (code "78") (name "VCC_IN") (class "Default")
      (node (ref "C20") (pin "2") (pinfunction "2_2") (pintype "passive"))
      (node (ref "C21") (pin "2") (pinfunction "2_2") (pintype "passive"))
      (node (ref "U7") (pin "3") (pinfunction "VIN_3") (pintype "passive"))
    )
    (net (code "79") (name "unconnected-(0.96_OLED-D2-Pad20)") (class "Default")
      (node (ref "0.96_OLED") (pin "20") (pinfunction "D2_20") (pintype "passive"))
    )
    (net (code "80") (name "unconnected-(0.96_OLED-NC-Pad7)") (class "Default")
      (node (ref "0.96_OLED") (pin "7") (pinfunction "NC_7") (pintype "passive+no_connect"))
    )
    (net (code "81") (name "unconnected-(C39-Pad2)") (class "Default")
      (node (ref "C39") (pin "2") (pinfunction "2_2") (pintype "passive"))
    )
    (net (code "82") (name "unconnected-(U2-OUT-Pad2)") (class "Default")
      (node (ref "U2") (pin "2") (pinfunction "OUT_2") (pintype "passive"))
    )
    (net (code "83") (name "unconnected-(U2-OUT-Pad4)") (class "Default")
      (node (ref "U2") (pin "4") (pinfunction "OUT_4") (pintype "passive"))
    )
    (net (code "84") (name "unconnected-(U6-VREF-Pad5)") (class "Default")
      (node (ref "U6") (pin "5") (pinfunction "VREF_5") (pintype "passive"))
    )
    (net (code "85") (name "unconnected-(U8-NC-Pad4)") (class "Default")
      (node (ref "U8") (pin "4") (pinfunction "NC_4") (pintype "passive+no_connect"))
    )
    (net (code "86") (name "unconnected-(U9-NC-Pad6)") (class "Default")
      (node (ref "U9") (pin "6") (pinfunction "NC_6") (pintype "passive+no_connect"))
    )
    (net (code "87") (name "unconnected-(U11-AUX_CL-Pad7)") (class "Default")
      (node (ref "U11") (pin "7") (pinfunction "AUX_CL_7") (pintype "passive+no_connect"))
    )
    (net (code "88") (name "unconnected-(U11-AUX_DA-Pad6)") (class "Default")
      (node (ref "U11") (pin "6") (pinfunction "AUX_DA_6") (pintype "passive+no_connect"))
    )
    (net (code "89") (name "unconnected-(U11-INT-Pad12)") (class "Default")
      (node (ref "U11") (pin "12") (pinfunction "INT_12") (pintype "passive"))
    )
    (net (code "90") (name "unconnected-(U11-NC-Pad2)") (class "Default")
      (node (ref "U11") (pin "2") (pinfunction "NC_2") (pintype "passive+no_connect"))
    )
    (net (code "91") (name "unconnected-(U11-NC-Pad3)") (class "Default")
      (node (ref "U11") (pin "3") (pinfunction "NC_3") (pintype "passive+no_connect"))
    )
    (net (code "92") (name "unconnected-(U11-NC-Pad4)") (class "Default")
      (node (ref "U11") (pin "4") (pinfunction "NC_4") (pintype "passive+no_connect"))
    )
    (net (code "93") (name "unconnected-(U11-NC-Pad5)") (class "Default")
      (node (ref "U11") (pin "5") (pinfunction "NC_5") (pintype "passive+no_connect"))
    )
    (net (code "94") (name "unconnected-(U11-NC-Pad14)") (class "Default")
      (node (ref "U11") (pin "14") (pinfunction "NC_14") (pintype "passive+no_connect"))
    )
    (net (code "95") (name "unconnected-(U11-NC-Pad15)") (class "Default")
      (node (ref "U11") (pin "15") (pinfunction "NC_15") (pintype "passive+no_connect"))
    )
    (net (code "96") (name "unconnected-(U11-NC-Pad16)") (class "Default")
      (node (ref "U11") (pin "16") (pinfunction "NC_16") (pintype "passive+no_connect"))
    )
    (net (code "97") (name "unconnected-(U11-NC-Pad17)") (class "Default")
      (node (ref "U11") (pin "17") (pinfunction "NC_17") (pintype "passive+no_connect"))
    )
    (net (code "98") (name "unconnected-(U11-RESV-Pad19)") (class "Default")
      (node (ref "U11") (pin "19") (pinfunction "RESV_19") (pintype "passive+no_connect"))
    )
    (net (code "99") (name "unconnected-(U11-RESV-Pad21)") (class "Default")
      (node (ref "U11") (pin "21") (pinfunction "RESV_21") (pintype "passive+no_connect"))
    )
    (net (code "100") (name "unconnected-(U11-RESV-Pad22)") (class "Default")
      (node (ref "U11") (pin "22") (pinfunction "RESV_22") (pintype "passive+no_connect"))
    )
    (net (code "101") (name "unconnected-(USB1-CC1-PadA5)") (class "Default")
      (node (ref "USB1") (pin "A5") (pinfunction "CC1_A5") (pintype "passive"))
    )
    (net (code "102") (name "unconnected-(USB1-CC2-PadB5)") (class "Default")
      (node (ref "USB1") (pin "B5") (pinfunction "CC2_B5") (pintype "passive"))
    )
    (net (code "103") (name "unconnected-(USB1-SBU1-PadA8)") (class "Default")
      (node (ref "USB1") (pin "A8") (pinfunction "SBU1_A8") (pintype "passive"))
    )
    (net (code "104") (name "unconnected-(USB1-SBU2-PadB8)") (class "Default")
      (node (ref "USB1") (pin "B8") (pinfunction "SBU2_B8") (pintype "passive"))
    )
    (net (code "105") (name "unconnected-(USB1-SSRXN1-PadB10)") (class "Default")
      (node (ref "USB1") (pin "B10") (pinfunction "SSRXN1_B10") (pintype "passive"))
    )
    (net (code "106") (name "unconnected-(USB1-SSRXN2-PadA10)") (class "Default")
      (node (ref "USB1") (pin "A10") (pinfunction "SSRXN2_A10") (pintype "passive"))
    )
    (net (code "107") (name "unconnected-(USB1-SSRXP1-PadB11)") (class "Default")
      (node (ref "USB1") (pin "B11") (pinfunction "SSRXP1_B11") (pintype "passive"))
    )
    (net (code "108") (name "unconnected-(USB1-SSRXP2-PadA11)") (class "Default")
      (node (ref "USB1") (pin "A11") (pinfunction "SSRXP2_A11") (pintype "passive"))
    )
    (net (code "109") (name "unconnected-(USB1-SSTXN1-PadA3)") (class "Default")
      (node (ref "USB1") (pin "A3") (pinfunction "SSTXN1_A3") (pintype "passive"))
    )
    (net (code "110") (name "unconnected-(USB1-SSTXN2-PadB3)") (class "Default")
      (node (ref "USB1") (pin "B3") (pinfunction "SSTXN2_B3") (pintype "passive"))
    )
    (net (code "111") (name "unconnected-(USB1-SSTXP1-PadA2)") (class "Default")
      (node (ref "USB1") (pin "A2") (pinfunction "SSTXP1_A2") (pintype "passive"))
    )
    (net (code "112") (name "unconnected-(USB1-SSTXP2-PadB2)") (class "Default")
      (node (ref "USB1") (pin "B2") (pinfunction "SSTXP2_B2") (pintype "passive"))
    )
  )
)
